# Mini_Arduino_5mm_RGB.net
KiCad netlist of a schematic drawn in EAGLE
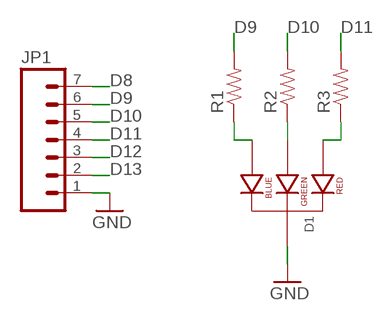
[diagram p0: schematic, sheet 1]

(export (version "E")
  (design (tool "Eeschema 10.0.6"))
  (components
    (comp (ref "D1")
      (value "LED-RGB-CC-THRUDIFFUSE")
      (footprint "eagle-import:LED-RGB-THRU")
      (libsource (lib "eagle-import") (part "LED-RGB-CC-THRUDIFFUSE"))
    )
    (comp (ref "JP1")
      (value "M07")
      (footprint "eagle-import:1X07")
      (libsource (lib "eagle-import") (part "M07"))
    )
    (comp (ref "R1")
      (value "RESISTORAXIAL-0.3")
      (footprint "eagle-import:AXIAL-0.3")
      (libsource (lib "eagle-import") (part "RESISTORAXIAL-0.3"))
    )
    (comp (ref "R2")
      (value "RESISTORAXIAL-0.3")
      (footprint "eagle-import:AXIAL-0.3")
      (libsource (lib "eagle-import") (part "RESISTORAXIAL-0.3"))
    )
    (comp (ref "R3")
      (value "RESISTORAXIAL-0.3")
      (footprint "eagle-import:AXIAL-0.3")
      (libsource (lib "eagle-import") (part "RESISTORAXIAL-0.3"))
    )
  )
  (nets
    (net (code "1") (name "/D8") (class "Default")
      (node (ref "JP1") (pin "7") (pinfunction "7_7") (pintype "passive"))
    )
    (net (code "2") (name "/D9") (class "Default")
      (node (ref "JP1") (pin "6") (pinfunction "6_6") (pintype "passive"))
      (node (ref "R1") (pin "P$2") (pinfunction "2_P$2") (pintype "passive"))
    )
    (net (code "3") (name "/D10") (class "Default")
      (node (ref "JP1") (pin "5") (pinfunction "5_5") (pintype "passive"))
      (node (ref "R2") (pin "P$2") (pinfunction "2_P$2") (pintype "passive"))
    )
    (net (code "4") (name "/D11") (class "Default")
      (node (ref "JP1") (pin "4") (pinfunction "4_4") (pintype "passive"))
      (node (ref "R3") (pin "P$2") (pinfunction "2_P$2") (pintype "passive"))
    )
    (net (code "5") (name "/D12") (class "Default")
      (node (ref "JP1") (pin "3") (pinfunction "3_3") (pintype "passive"))
    )
    (net (code "6") (name "/D13") (class "Default")
      (node (ref "JP1") (pin "2") (pinfunction "2_2") (pintype "passive"))
    )
    (net (code "7") (name "GND") (class "Default")
      (node (ref "D1") (pin "2") (pinfunction "CATHODE_2") (pintype "bidirectional"))
      (node (ref "JP1") (pin "1") (pinfunction "1_1") (pintype "passive"))
    )
    (net (code "8") (name "Net-(D1-BLUE_CATHODE)") (class "Default")
      (node (ref "D1") (pin "4") (pinfunction "BLUE_CATHODE_4") (pintype "bidirectional"))
      (node (ref "R1") (pin "P$1") (pinfunction "1_P$1") (pintype "passive"))
    )
    (net (code "9") (name "Net-(D1-GREEN_CATHODE)") (class "Default")
      (node (ref "D1") (pin "3") (pinfunction "GREEN_CATHODE_3") (pintype "bidirectional"))
      (node (ref "R2") (pin "P$1") (pinfunction "1_P$1") (pintype "passive"))
    )
    (net (code "10") (name "Net-(D1-RED_CATHODE)") (class "Default")
      (node (ref "D1") (pin "1") (pinfunction "RED_CATHODE_1") (pintype "bidirectional"))
      (node (ref "R3") (pin "P$1") (pinfunction "1_P$1") (pintype "passive"))
    )
  )
)
